# Supply_Switches_for_3V3_externals.net
KiCad netlist of a schematic drawn in Altium Designer
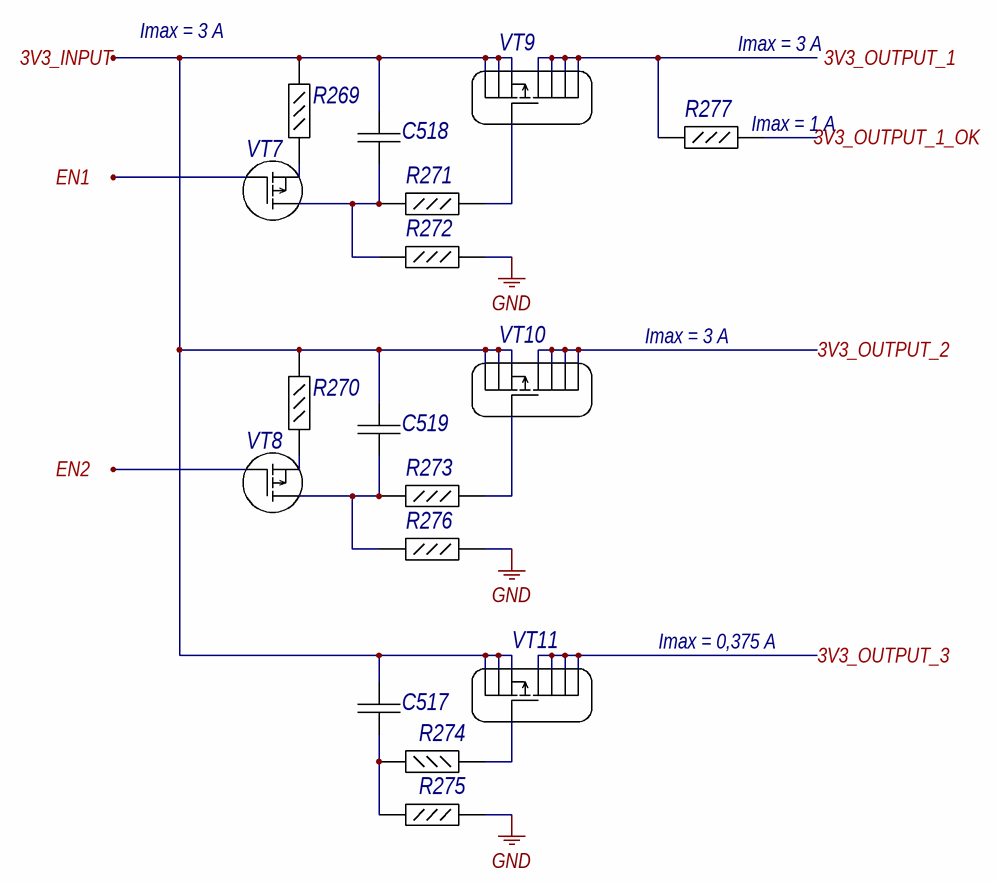
[diagram p0: Supply Switches for 3V3 externals.SchDoc]

(export (version "E")
  (design (tool "Eeschema 10.0.6"))
  (components
    (comp (ref "C517")
      (value "CGB2A1X5R1E105K033BC")
      (footprint "CAPC1005X33X10LL5")
      (description "Chip Capacitor, 1 uF, +/- 10%, 25 V, -55 to 85 degC, 0402 (1005 Metric), RoHS, Tape and Reel")
      (fields (field (name "TOLERANCE") "10%"))
      (libsource (lib "MiniPC DB") (part "CAP_NP"))
    )
    (comp (ref "C518")
      (value "CGB2A1X5R1E105K033BC")
      (footprint "CAPC1005X33X10LL5")
      (description "Chip Capacitor, 1 uF, +/- 10%, 25 V, -55 to 85 degC, 0402 (1005 Metric), RoHS, Tape and Reel")
      (fields (field (name "TOLERANCE") "10%"))
      (libsource (lib "MiniPC DB") (part "CAP_NP"))
    )
    (comp (ref "C519")
      (value "CGB2A1X5R1E105K033BC")
      (footprint "CAPC1005X33X10LL5")
      (description "Chip Capacitor, 1 uF, +/- 10%, 25 V, -55 to 85 degC, 0402 (1005 Metric), RoHS, Tape and Reel")
      (fields (field (name "TOLERANCE") "10%"))
      (libsource (lib "MiniPC DB") (part "CAP_NP"))
    )
    (comp (ref "R269")
      (value "ERJ-2RKF10R0X")
      (footprint "RESC1005X40X25LL05T05")
      (description "Chip Resistor, 10 Ohm, +/- 1%, 100 mW, -55 to 155 degC, 0402 (1005 Metric), RoHS, Tape and Reel")
      (fields (field (name "TOLERANCE") "1%") (field (name "MANUFACTURER") "Basic Passives"))
      (libsource (lib "") (part "RES-0.05_1"))
    )
    (comp (ref "R270")
      (value "ERJ-2RKF10R0X")
      (footprint "RESC1005X40X25LL05T05")
      (description "Chip Resistor, 10 Ohm, +/- 1%, 100 mW, -55 to 155 degC, 0402 (1005 Metric), RoHS, Tape and Reel")
      (fields (field (name "TOLERANCE") "1%") (field (name "MANUFACTURER") "Basic Passives"))
      (libsource (lib "") (part "RES-0.05_1"))
    )
    (comp (ref "R271")
      (value "ERJ-2RKF10R0X")
      (footprint "RESC1005X40X25LL05T05")
      (description "Chip Resistor, 10 Ohm, +/- 1%, 100 mW, -55 to 155 degC, 0402 (1005 Metric), RoHS, Tape and Reel")
      (fields (field (name "TOLERANCE") "1%") (field (name "MANUFACTURER") "Basic Passives"))
      (libsource (lib "") (part "RES-0.05_1"))
    )
    (comp (ref "R272")
      (value "ERJ-2RKF1003X")
      (footprint "RESC1005X40X25LL05T05")
      (description "Chip Resistor, 100 KOhm, +/- 1%, 100 mW, -55 to 155 degC, 0402 (1005 Metric), RoHS, Tape and Reel")
      (fields (field (name "TOLERANCE") "1%") (field (name "MANUFACTURER") "Basic Passives"))
      (libsource (lib "") (part "RES-0.05_2"))
    )
    (comp (ref "R273")
      (value "ERJ-2RKF10R0X")
      (footprint "RESC1005X40X25LL05T05")
      (description "Chip Resistor, 10 Ohm, +/- 1%, 100 mW, -55 to 155 degC, 0402 (1005 Metric), RoHS, Tape and Reel")
      (fields (field (name "TOLERANCE") "1%") (field (name "MANUFACTURER") "Basic Passives"))
      (libsource (lib "") (part "RES-0.05_1"))
    )
    (comp (ref "R274")
      (value "ERJ-2RKF10R0X")
      (footprint "RESC1005X40X25LL05T05")
      (description "Chip Resistor, 10 Ohm, +/- 1%, 100 mW, -55 to 155 degC, 0402 (1005 Metric), RoHS, Tape and Reel")
      (fields (field (name "TOLERANCE") "1%") (field (name "MANUFACTURER") "Basic Passives"))
      (libsource (lib "MiniPC DB") (part "RES-0.05"))
    )
    (comp (ref "R275")
      (value "ERJ-2RKF1003X")
      (footprint "RESC1005X40X25LL05T05")
      (description "Chip Resistor, 100 KOhm, +/- 1%, 100 mW, -55 to 155 degC, 0402 (1005 Metric), RoHS, Tape and Reel")
      (fields (field (name "TOLERANCE") "1%") (field (name "MANUFACTURER") "Basic Passives"))
      (libsource (lib "") (part "RES-0.05_2"))
    )
    (comp (ref "R276")
      (value "ERJ-2RKF1003X")
      (footprint "RESC1005X40X25LL05T05")
      (description "Chip Resistor, 100 KOhm, +/- 1%, 100 mW, -55 to 155 degC, 0402 (1005 Metric), RoHS, Tape and Reel")
      (fields (field (name "TOLERANCE") "1%") (field (name "MANUFACTURER") "Basic Passives"))
      (libsource (lib "") (part "RES-0.05_2"))
    )
    (comp (ref "R277")
      (value "ERJ-2RKF1003X")
      (footprint "RESC1005X40X25LL05T05")
      (description "Chip Resistor, 100 KOhm, +/- 1%, 100 mW, -55 to 155 degC, 0402 (1005 Metric), RoHS, Tape and Reel")
      (fields (field (name "TOLERANCE") "1%") (field (name "MANUFACTURER") "Basic Passives"))
      (libsource (lib "") (part "RES-0.05_2"))
    )
    (comp (ref "VT7")
      (value "DMG2305UX-7")
      (footprint "DIOD-SOT23-3_A_V")
      (description "P-Channel Enhancement Mode MOSFET, 20 V, -55 to 150 degC, 3-Pin SOT23, RoHS, Tape and Reel")
      (fields (field (name "MANUFACTURER") "Diodes Inc"))
      (libsource (lib "MiniPC DB") (part "MOSFET-P-IND"))
    )
    (comp (ref "VT8")
      (value "DMG2305UX-7")
      (footprint "DIOD-SOT23-3_A_V")
      (description "P-Channel Enhancement Mode MOSFET, 20 V, -55 to 150 degC, 3-Pin SOT23, RoHS, Tape and Reel")
      (fields (field (name "MANUFACTURER") "Diodes Inc"))
      (libsource (lib "MiniPC DB") (part "MOSFET-P-IND"))
    )
    (comp (ref "VT9")
      (value "SiSS23DN-T1-GE3")
      (footprint "VISH-PPAK1212-8S_V")
      (description "P-Channel MOSFET, 20 V, -50 to 150 degC, 8-Pin SMD (PPAK1212-8S), RoHS, Tape and Reel")
      (libsource (lib "MiniPC DB") (part "MOSFET-P-IND_2"))
    )
    (comp (ref "VT10")
      (value "SiSS23DN-T1-GE3")
      (footprint "VISH-PPAK1212-8S_V")
      (description "P-Channel MOSFET, 20 V, -50 to 150 degC, 8-Pin SMD (PPAK1212-8S), RoHS, Tape and Reel")
      (libsource (lib "MiniPC DB") (part "MOSFET-P-IND_2"))
    )
    (comp (ref "VT11")
      (value "SiSS23DN-T1-GE3")
      (footprint "VISH-PPAK1212-8S_V")
      (description "P-Channel MOSFET, 20 V, -50 to 150 degC, 8-Pin SMD (PPAK1212-8S), RoHS, Tape and Reel")
      (libsource (lib "MiniPC DB") (part "MOSFET-P-IND_2"))
    )
  )
  (nets
    (net (code "1") (name "/3V3_INPUT") (class "Default")
      (node (ref "C517") (pin "2") (pinfunction "2_2") (pintype "passive"))
      (node (ref "C518") (pin "2") (pinfunction "2_2") (pintype "passive"))
      (node (ref "C519") (pin "2") (pinfunction "2_2") (pintype "passive"))
      (node (ref "R269") (pin "2") (pinfunction "2_2") (pintype "passive"))
      (node (ref "R270") (pin "2") (pinfunction "2_2") (pintype "passive"))
      (node (ref "VT10") (pin "1") (pinfunction "S_1") (pintype "passive"))
      (node (ref "VT10") (pin "2") (pinfunction "S_2") (pintype "passive"))
      (node (ref "VT10") (pin "3") (pinfunction "S_3") (pintype "passive"))
      (node (ref "VT11") (pin "1") (pinfunction "S_1") (pintype "passive"))
      (node (ref "VT11") (pin "2") (pinfunction "S_2") (pintype "passive"))
      (node (ref "VT11") (pin "3") (pinfunction "S_3") (pintype "passive"))
      (node (ref "VT9") (pin "1") (pinfunction "S_1") (pintype "passive"))
      (node (ref "VT9") (pin "2") (pinfunction "S_2") (pintype "passive"))
      (node (ref "VT9") (pin "3") (pinfunction "S_3") (pintype "passive"))
    )
    (net (code "2") (name "/3V3_OUTPUT_1") (class "Default")
      (node (ref "R277") (pin "2") (pinfunction "2_2") (pintype "passive"))
      (node (ref "VT9") (pin "5") (pinfunction "D_5") (pintype "passive"))
      (node (ref "VT9") (pin "6") (pinfunction "D_6") (pintype "passive"))
      (node (ref "VT9") (pin "7") (pinfunction "D_7") (pintype "passive"))
      (node (ref "VT9") (pin "8") (pinfunction "D_8") (pintype "passive"))
    )
    (net (code "3") (name "/3V3_OUTPUT_1_OK") (class "Default")
      (node (ref "R277") (pin "1") (pinfunction "1_1") (pintype "passive"))
    )
    (net (code "4") (name "/3V3_OUTPUT_2") (class "Default")
      (node (ref "VT10") (pin "5") (pinfunction "D_5") (pintype "passive"))
      (node (ref "VT10") (pin "6") (pinfunction "D_6") (pintype "passive"))
      (node (ref "VT10") (pin "7") (pinfunction "D_7") (pintype "passive"))
      (node (ref "VT10") (pin "8") (pinfunction "D_8") (pintype "passive"))
    )
    (net (code "5") (name "/3V3_OUTPUT_3") (class "Default")
      (node (ref "VT11") (pin "5") (pinfunction "D_5") (pintype "passive"))
      (node (ref "VT11") (pin "6") (pinfunction "D_6") (pintype "passive"))
      (node (ref "VT11") (pin "7") (pinfunction "D_7") (pintype "passive"))
      (node (ref "VT11") (pin "8") (pinfunction "D_8") (pintype "passive"))
    )
    (net (code "6") (name "/EN1") (class "Default")
      (node (ref "VT7") (pin "1") (pinfunction "1_1") (pintype "passive"))
    )
    (net (code "7") (name "/EN2") (class "Default")
      (node (ref "VT8") (pin "1") (pinfunction "1_1") (pintype "passive"))
    )
    (net (code "8") (name "GND") (class "Default")
      (node (ref "R272") (pin "1") (pinfunction "1_1") (pintype "passive"))
      (node (ref "R275") (pin "1") (pinfunction "1_1") (pintype "passive"))
      (node (ref "R276") (pin "1") (pinfunction "1_1") (pintype "passive"))
    )
    (net (code "9") (name "Net-(C517-Pad1)") (class "Default")
      (node (ref "C517") (pin "1") (pinfunction "1_1") (pintype "passive"))
      (node (ref "R274") (pin "1") (pinfunction "1_1") (pintype "passive"))
      (node (ref "R275") (pin "2") (pinfunction "2_2") (pintype "passive"))
    )
    (net (code "10") (name "Net-(C518-Pad1)") (class "Default")
      (node (ref "C518") (pin "1") (pinfunction "1_1") (pintype "passive"))
      (node (ref "R271") (pin "1") (pinfunction "1_1") (pintype "passive"))
      (node (ref "R272") (pin "2") (pinfunction "2_2") (pintype "passive"))
      (node (ref "VT7") (pin "3") (pinfunction "3_3") (pintype "passive"))
    )
    (net (code "11") (name "Net-(C519-Pad1)") (class "Default")
      (node (ref "C519") (pin "1") (pinfunction "1_1") (pintype "passive"))
      (node (ref "R273") (pin "1") (pinfunction "1_1") (pintype "passive"))
      (node (ref "R276") (pin "2") (pinfunction "2_2") (pintype "passive"))
      (node (ref "VT8") (pin "3") (pinfunction "3_3") (pintype "passive"))
    )
    (net (code "12") (name "Net-(R269-Pad1)") (class "Default")
      (node (ref "R269") (pin "1") (pinfunction "1_1") (pintype "passive"))
      (node (ref "VT7") (pin "2") (pinfunction "2_2") (pintype "passive"))
    )
    (net (code "13") (name "Net-(R270-Pad1)") (class "Default")
      (node (ref "R270") (pin "1") (pinfunction "1_1") (pintype "passive"))
      (node (ref "VT8") (pin "2") (pinfunction "2_2") (pintype "passive"))
    )
    (net (code "14") (name "Net-(VT9-G)") (class "Default")
      (node (ref "R271") (pin "2") (pinfunction "2_2") (pintype "passive"))
      (node (ref "VT9") (pin "4") (pinfunction "G_4") (pintype "passive"))
    )
    (net (code "15") (name "Net-(VT10-G)") (class "Default")
      (node (ref "R273") (pin "2") (pinfunction "2_2") (pintype "passive"))
      (node (ref "VT10") (pin "4") (pinfunction "G_4") (pintype "passive"))
    )
    (net (code "16") (name "Net-(VT11-G)") (class "Default")
      (node (ref "R274") (pin "2") (pinfunction "2_2") (pintype "passive"))
      (node (ref "VT11") (pin "4") (pinfunction "G_4") (pintype "passive"))
    )
  )
)
